# 1-voice_2_2.net
KiCad netlist of a schematic drawn in EAGLE
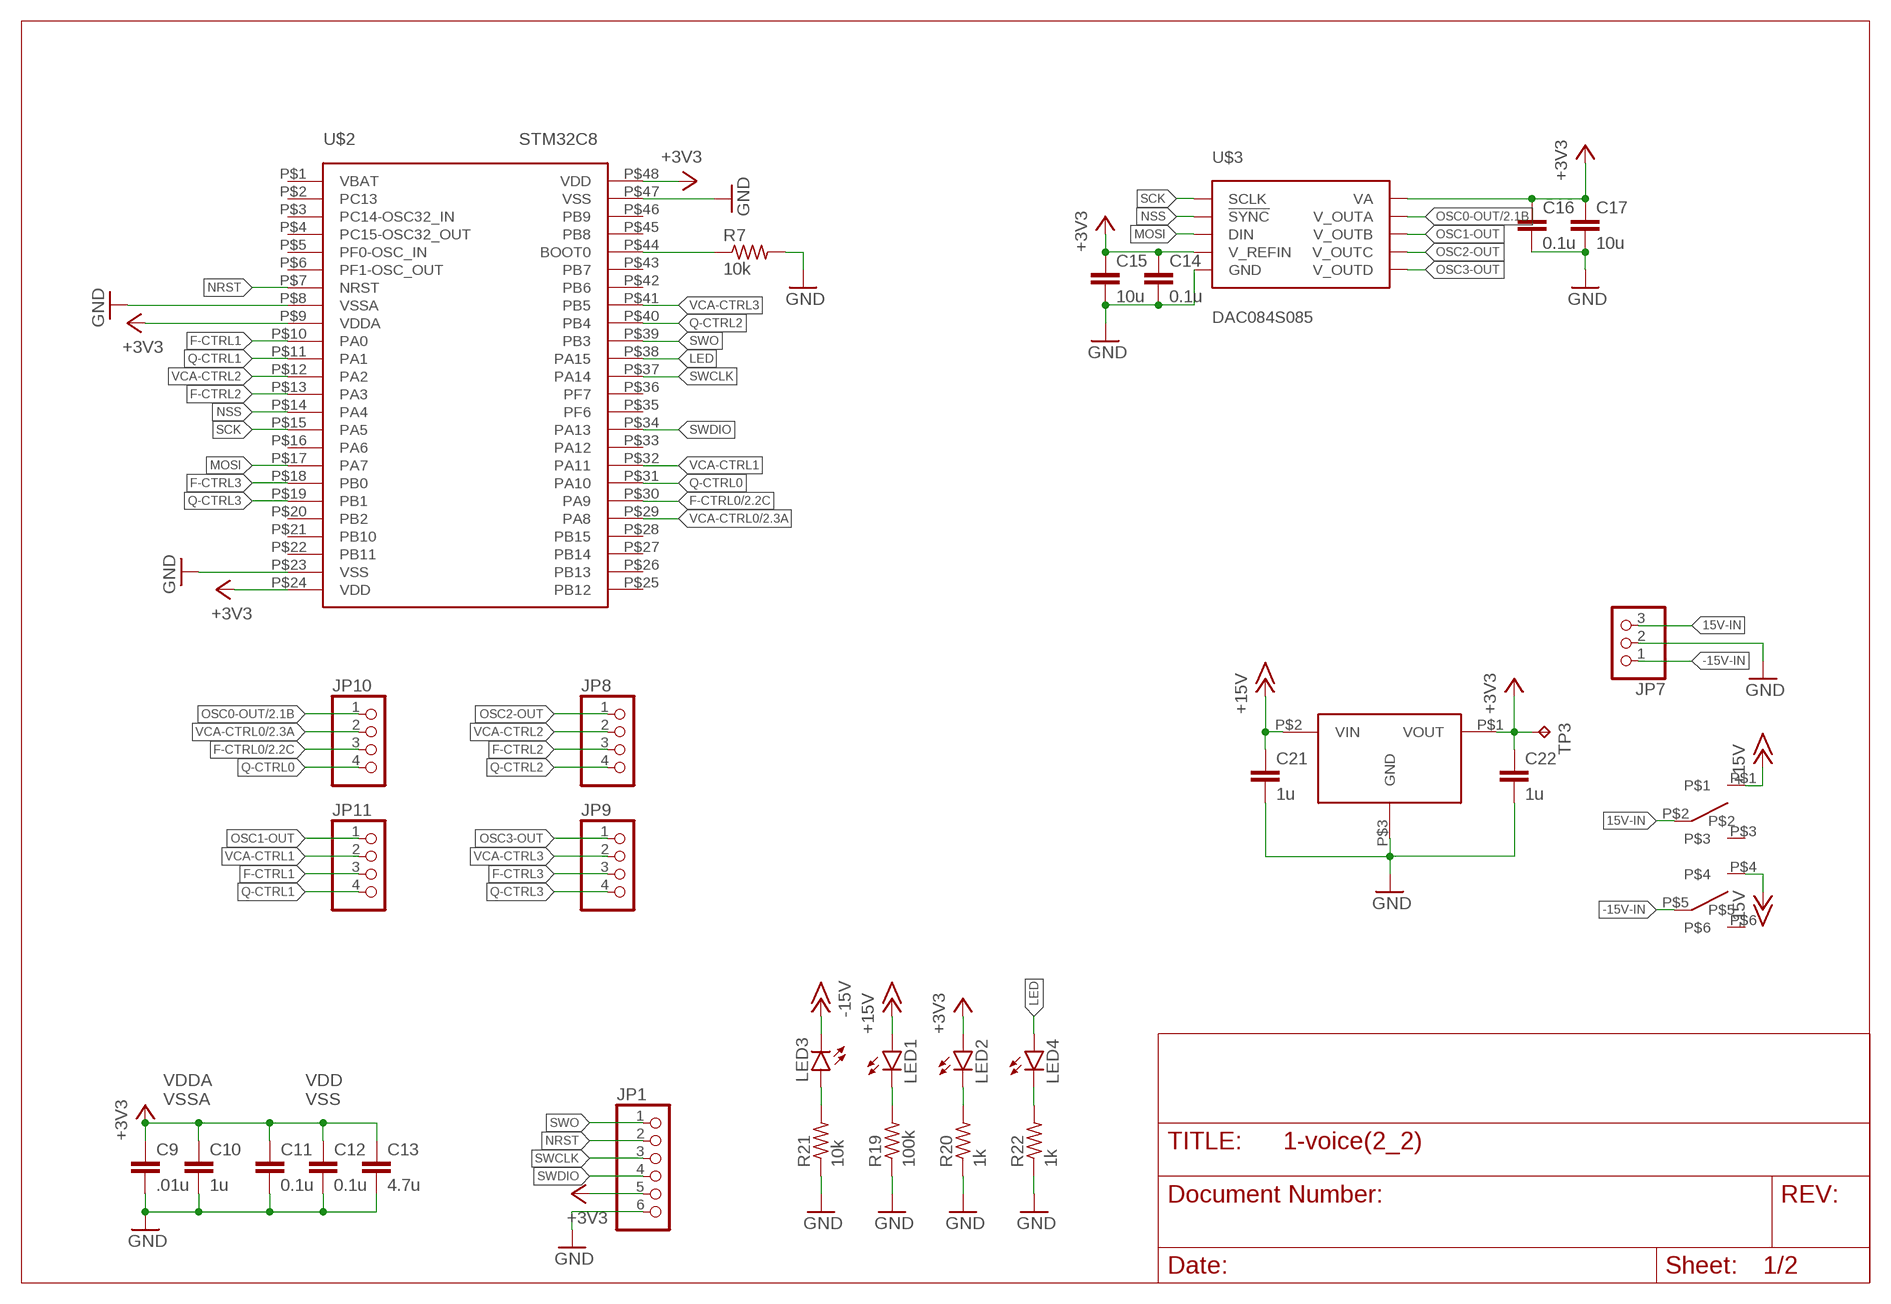
[diagram p0: schematic, sheet 1]
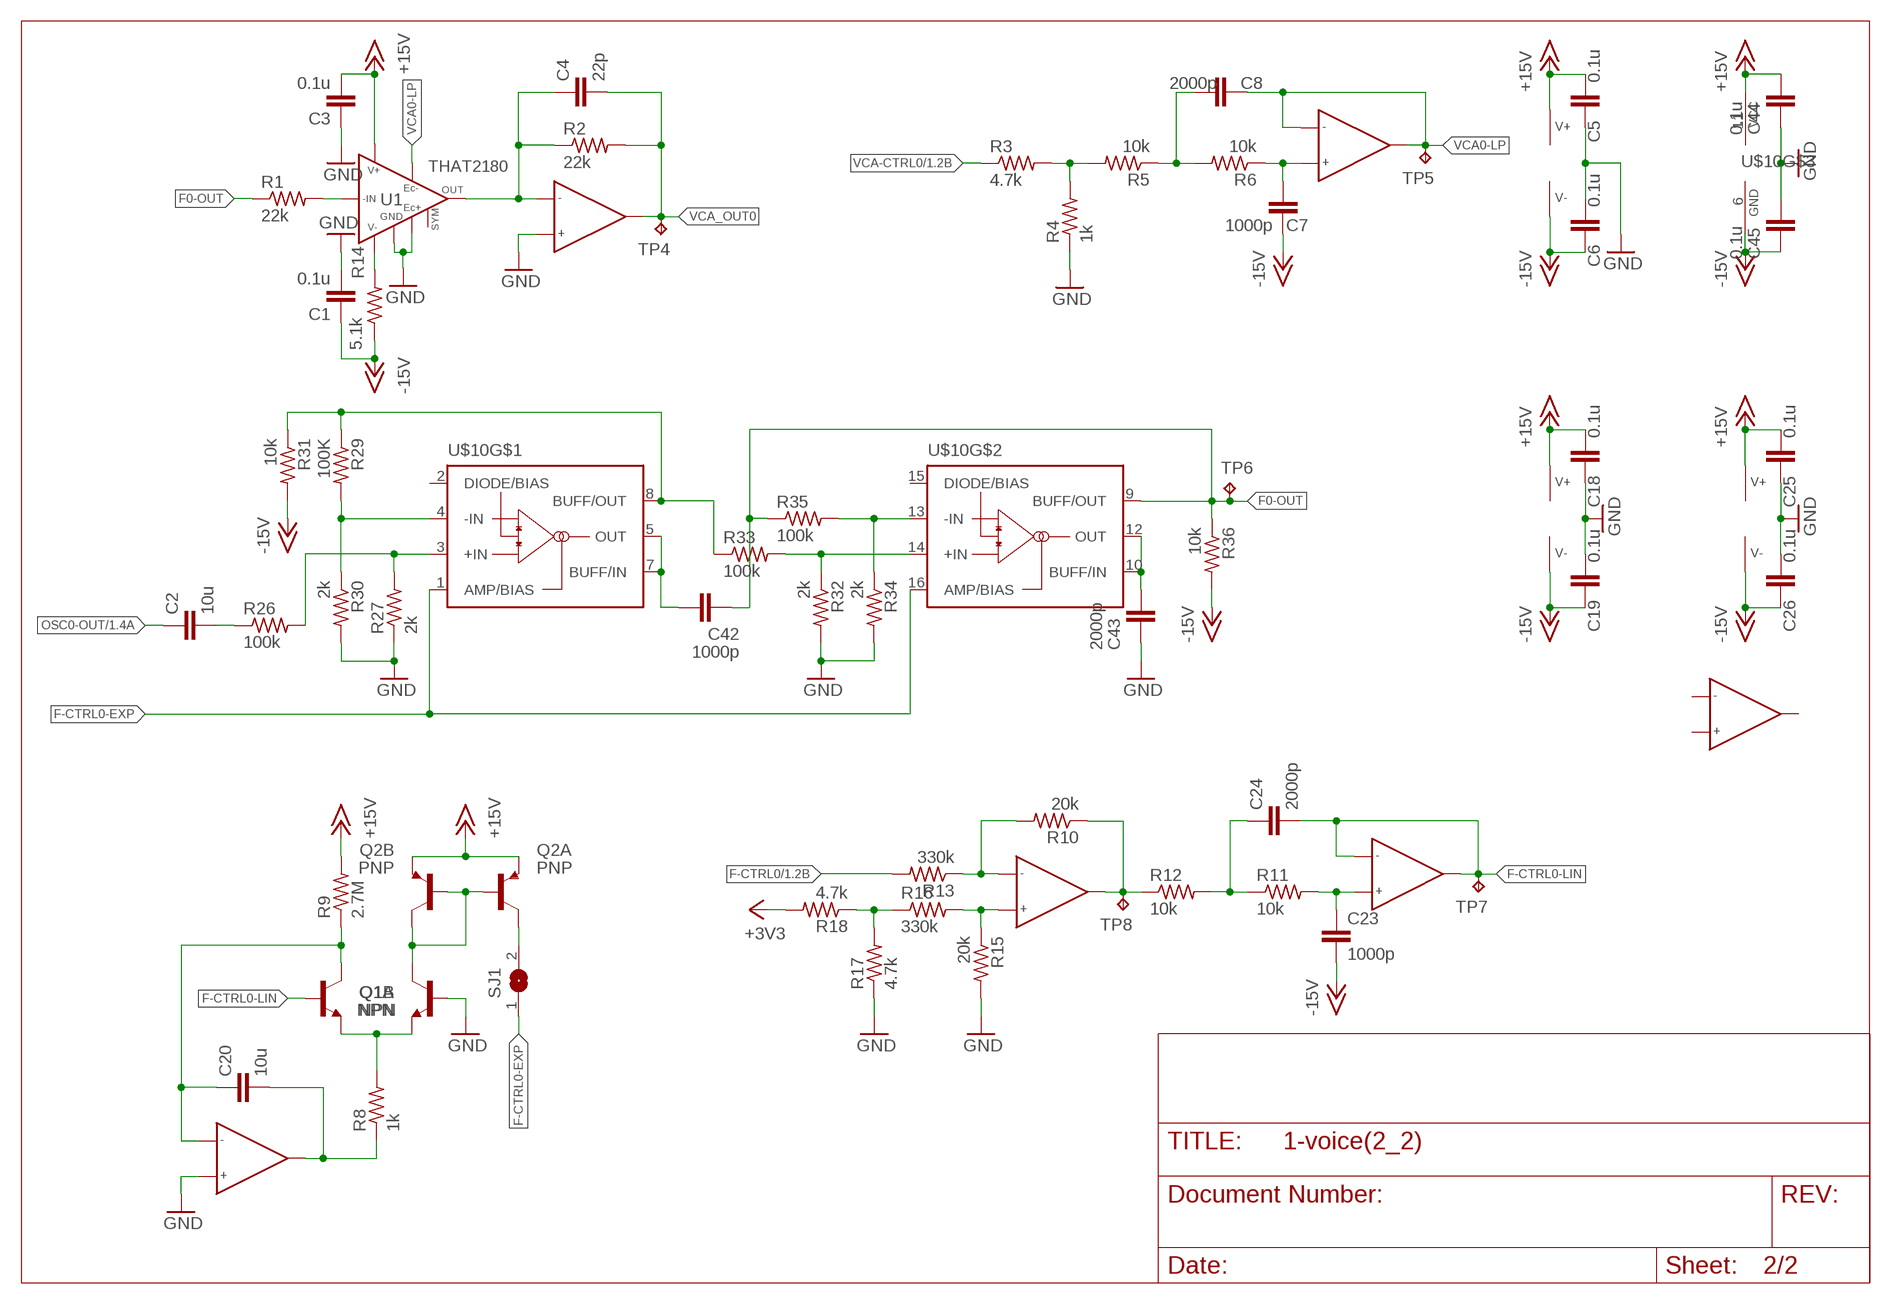
[diagram p1: schematic, sheet 2]

(export (version "E")
  (design (tool "Eeschema 10.0.6"))
  (components
    (comp (ref "C1")
      (value "0.1u")
      (footprint "eagle-import:C0603")
      (libsource (lib "eagle-import") (part "C-EUC0603"))
    )
    (comp (ref "C2")
      (value "10u")
      (footprint "eagle-import:C0603")
      (libsource (lib "eagle-import") (part "C-EUC0603"))
    )
    (comp (ref "C3")
      (value "0.1u")
      (footprint "eagle-import:C0603")
      (libsource (lib "eagle-import") (part "C-EUC0603"))
    )
    (comp (ref "C4")
      (value "22p")
      (footprint "eagle-import:C0603")
      (libsource (lib "eagle-import") (part "C-EUC0603"))
    )
    (comp (ref "C5")
      (value "0.1u")
      (footprint "eagle-import:C0603")
      (libsource (lib "eagle-import") (part "C-EUC0603"))
    )
    (comp (ref "C6")
      (value "0.1u")
      (footprint "eagle-import:C0603")
      (libsource (lib "eagle-import") (part "C-EUC0603"))
    )
    (comp (ref "C7")
      (value "1000p")
      (footprint "eagle-import:C0603")
      (libsource (lib "eagle-import") (part "C-EUC0603"))
    )
    (comp (ref "C8")
      (value "2000p")
      (footprint "eagle-import:C0603")
      (libsource (lib "eagle-import") (part "C-EUC0603"))
    )
    (comp (ref "C18")
      (value "0.1u")
      (footprint "eagle-import:C0603")
      (libsource (lib "eagle-import") (part "C-EUC0603"))
    )
    (comp (ref "C19")
      (value "0.1u")
      (footprint "eagle-import:C0603")
      (libsource (lib "eagle-import") (part "C-EUC0603"))
    )
    (comp (ref "C20")
      (value "10u")
      (footprint "eagle-import:C0603")
      (libsource (lib "eagle-import") (part "C-EUC0603"))
    )
    (comp (ref "C23")
      (value "1000p")
      (footprint "eagle-import:C0603")
      (libsource (lib "eagle-import") (part "C-EUC0603"))
    )
    (comp (ref "C24")
      (value "2000p")
      (footprint "eagle-import:C0603")
      (libsource (lib "eagle-import") (part "C-EUC0603"))
    )
    (comp (ref "C25")
      (value "0.1u")
      (footprint "eagle-import:C0603")
      (libsource (lib "eagle-import") (part "C-EUC0603"))
    )
    (comp (ref "C26")
      (value "0.1u")
      (footprint "eagle-import:C0603")
      (libsource (lib "eagle-import") (part "C-EUC0603"))
    )
    (comp (ref "C42")
      (value "1000p")
      (footprint "eagle-import:C0603")
      (libsource (lib "eagle-import") (part "C-EUC0603"))
    )
    (comp (ref "C43")
      (value "2000p")
      (footprint "eagle-import:C0603")
      (libsource (lib "eagle-import") (part "C-EUC0603"))
    )
    (comp (ref "C44")
      (value "0.1u")
      (footprint "eagle-import:C0603")
      (libsource (lib "eagle-import") (part "C-EUC0603"))
    )
    (comp (ref "C45")
      (value "0.1u")
      (footprint "eagle-import:C0603")
      (libsource (lib "eagle-import") (part "C-EUC0603"))
    )
    (comp (ref "Q1")
      (value "NPN")
      (footprint "eagle-import:SOT-363-JBLMASK")
      (libsource (lib "eagle-import") (part "TRANS-BJT_NPN-DUAL-BC847BS-JBLMASK"))
    )
    (comp (ref "Q2")
      (value "PNP")
      (footprint "eagle-import:SOT-363-JBLMASK")
      (libsource (lib "eagle-import") (part "TRANS-BJT_PNP-DUAL-BC857-JBLMASK"))
    )
    (comp (ref "R1")
      (value "22k")
      (footprint "eagle-import:R0603")
      (libsource (lib "eagle-import") (part "R-US_R0603"))
    )
    (comp (ref "R2")
      (value "22k")
      (footprint "eagle-import:R0603")
      (libsource (lib "eagle-import") (part "R-US_R0603"))
    )
    (comp (ref "R3")
      (value "4.7k")
      (footprint "eagle-import:R0603")
      (libsource (lib "eagle-import") (part "R-US_R0603"))
    )
    (comp (ref "R4")
      (value "1k")
      (footprint "eagle-import:R0603")
      (libsource (lib "eagle-import") (part "R-US_R0603"))
    )
    (comp (ref "R5")
      (value "10k")
      (footprint "eagle-import:R0603")
      (libsource (lib "eagle-import") (part "R-US_R0603"))
    )
    (comp (ref "R6")
      (value "10k")
      (footprint "eagle-import:R0603")
      (libsource (lib "eagle-import") (part "R-US_R0603"))
    )
    (comp (ref "R8")
      (value "1k")
      (footprint "eagle-import:R0603")
      (libsource (lib "eagle-import") (part "R-US_R0603"))
    )
    (comp (ref "R9")
      (value "2.7M")
      (footprint "eagle-import:R0603")
      (libsource (lib "eagle-import") (part "R-US_R0603"))
    )
    (comp (ref "R10")
      (value "20k")
      (footprint "eagle-import:R0603")
      (libsource (lib "eagle-import") (part "R-US_R0603"))
    )
    (comp (ref "R11")
      (value "10k")
      (footprint "eagle-import:R0603")
      (libsource (lib "eagle-import") (part "R-US_R0603"))
    )
    (comp (ref "R12")
      (value "10k")
      (footprint "eagle-import:R0603")
      (libsource (lib "eagle-import") (part "R-US_R0603"))
    )
    (comp (ref "R13")
      (value "330k")
      (footprint "eagle-import:R0603")
      (libsource (lib "eagle-import") (part "R-US_R0603"))
    )
    (comp (ref "R14")
      (value "5.1k")
      (footprint "eagle-import:R0603")
      (libsource (lib "eagle-import") (part "R-US_R0603"))
    )
    (comp (ref "R15")
      (value "20k")
      (footprint "eagle-import:R0603")
      (libsource (lib "eagle-import") (part "R-US_R0603"))
    )
    (comp (ref "R16")
      (value "330k")
      (footprint "eagle-import:R0603")
      (libsource (lib "eagle-import") (part "R-US_R0603"))
    )
    (comp (ref "R17")
      (value "4.7k")
      (footprint "eagle-import:R0603")
      (libsource (lib "eagle-import") (part "R-US_R0603"))
    )
    (comp (ref "R18")
      (value "4.7k")
      (footprint "eagle-import:R0603")
      (libsource (lib "eagle-import") (part "R-US_R0603"))
    )
    (comp (ref "R26")
      (value "100k")
      (footprint "eagle-import:R0603")
      (libsource (lib "eagle-import") (part "R-US_R0603"))
    )
    (comp (ref "R27")
      (value "2k")
      (footprint "eagle-import:R0603")
      (libsource (lib "eagle-import") (part "R-US_R0603"))
    )
    (comp (ref "R29")
      (value "100K")
      (footprint "eagle-import:R0603")
      (libsource (lib "eagle-import") (part "R-US_R0603"))
    )
    (comp (ref "R30")
      (value "2k")
      (footprint "eagle-import:R0603")
      (libsource (lib "eagle-import") (part "R-US_R0603"))
    )
    (comp (ref "R31")
      (value "10k")
      (footprint "eagle-import:R0603")
      (libsource (lib "eagle-import") (part "R-US_R0603"))
    )
    (comp (ref "R32")
      (value "2k")
      (footprint "eagle-import:R0603")
      (libsource (lib "eagle-import") (part "R-US_R0603"))
    )
    (comp (ref "R33")
      (value "100k")
      (footprint "eagle-import:R0603")
      (libsource (lib "eagle-import") (part "R-US_R0603"))
    )
    (comp (ref "R34")
      (value "2k")
      (footprint "eagle-import:R0603")
      (libsource (lib "eagle-import") (part "R-US_R0603"))
    )
    (comp (ref "R35")
      (value "100k")
      (footprint "eagle-import:R0603")
      (libsource (lib "eagle-import") (part "R-US_R0603"))
    )
    (comp (ref "R36")
      (value "10k")
      (footprint "eagle-import:R0603")
      (libsource (lib "eagle-import") (part "R-US_R0603"))
    )
    (comp (ref "SJ1") (value "SJ") (footprint "eagle-import:SJ") (libsource (lib "eagle-import") (part "SJ")))
    (comp (ref "TP4")
      (value "TPPAD1-13")
      (footprint "eagle-import:P1-13")
      (libsource (lib "eagle-import") (part "TPPAD1-13"))
    )
    (comp (ref "TP5")
      (value "TPPAD1-13")
      (footprint "eagle-import:P1-13")
      (libsource (lib "eagle-import") (part "TPPAD1-13"))
    )
    (comp (ref "TP6")
      (value "TPPAD1-13")
      (footprint "eagle-import:P1-13")
      (libsource (lib "eagle-import") (part "TPPAD1-13"))
    )
    (comp (ref "TP7")
      (value "TPPAD1-13")
      (footprint "eagle-import:P1-13")
      (libsource (lib "eagle-import") (part "TPPAD1-13"))
    )
    (comp (ref "TP8")
      (value "TPPAD1-13")
      (footprint "eagle-import:P1-13")
      (libsource (lib "eagle-import") (part "TPPAD1-13"))
    )
    (comp (ref "U$1")
      (value "TL072")
      (footprint "eagle-import:SOIC8")
      (libsource (lib "eagle-import") (part "TL072"))
    )
    (comp (ref "U$5")
      (value "TL072")
      (footprint "eagle-import:SOIC8")
      (libsource (lib "eagle-import") (part "TL072"))
    )
    (comp (ref "U$10")
      (value "XX-13700DMP16")
      (footprint "eagle-import:DMP16")
      (libsource (lib "eagle-import") (part "XX-13700DMP16"))
    )
    (comp (ref "U$11")
      (value "TL072")
      (footprint "eagle-import:SOIC8")
      (libsource (lib "eagle-import") (part "TL072"))
    )
    (comp (ref "U1")
      (value "THAT2180")
      (footprint "eagle-import:SIP8")
      (libsource (lib "eagle-import") (part "THAT2180"))
    )
    (comp (ref "C9")
      (value ".01u")
      (footprint "eagle-import:C0603")
      (libsource (lib "eagle-import") (part "C-EUC0603"))
    )
    (comp (ref "C10")
      (value "1u")
      (footprint "eagle-import:C0603")
      (libsource (lib "eagle-import") (part "C-EUC0603"))
    )
    (comp (ref "C11")
      (value "0.1u")
      (footprint "eagle-import:C0603")
      (libsource (lib "eagle-import") (part "C-EUC0603"))
    )
    (comp (ref "C12")
      (value "0.1u")
      (footprint "eagle-import:C0603")
      (libsource (lib "eagle-import") (part "C-EUC0603"))
    )
    (comp (ref "C13")
      (value "4.7u")
      (footprint "eagle-import:C0603")
      (libsource (lib "eagle-import") (part "C-EUC0603"))
    )
    (comp (ref "C14")
      (value "0.1u")
      (footprint "eagle-import:C0603")
      (libsource (lib "eagle-import") (part "C-EUC0603"))
    )
    (comp (ref "C15")
      (value "10u")
      (footprint "eagle-import:C0603")
      (libsource (lib "eagle-import") (part "C-EUC0603"))
    )
    (comp (ref "C16")
      (value "0.1u")
      (footprint "eagle-import:C0603")
      (libsource (lib "eagle-import") (part "C-EUC0603"))
    )
    (comp (ref "C17")
      (value "10u")
      (footprint "eagle-import:C0603")
      (libsource (lib "eagle-import") (part "C-EUC0603"))
    )
    (comp (ref "C21")
      (value "1u")
      (footprint "eagle-import:C0603")
      (libsource (lib "eagle-import") (part "C-EUC0603"))
    )
    (comp (ref "C22")
      (value "1u")
      (footprint "eagle-import:C0603")
      (libsource (lib "eagle-import") (part "C-EUC0603"))
    )
    (comp (ref "JP1")
      (value "PINHD-1X6")
      (footprint "eagle-import:1X06")
      (libsource (lib "eagle-import") (part "PINHD-1X6"))
    )
    (comp (ref "JP7")
      (value "PINHD-1X3")
      (footprint "eagle-import:1X03")
      (libsource (lib "eagle-import") (part "PINHD-1X3"))
    )
    (comp (ref "JP8")
      (value "PINHD-1X4")
      (footprint "eagle-import:1X04")
      (libsource (lib "eagle-import") (part "PINHD-1X4"))
    )
    (comp (ref "JP9")
      (value "PINHD-1X4")
      (footprint "eagle-import:1X04")
      (libsource (lib "eagle-import") (part "PINHD-1X4"))
    )
    (comp (ref "JP10")
      (value "PINHD-1X4")
      (footprint "eagle-import:1X04")
      (libsource (lib "eagle-import") (part "PINHD-1X4"))
    )
    (comp (ref "JP11")
      (value "PINHD-1X4")
      (footprint "eagle-import:1X04")
      (libsource (lib "eagle-import") (part "PINHD-1X4"))
    )
    (comp (ref "LED1")
      (value "LEDSMT1206")
      (footprint "eagle-import:1206")
      (libsource (lib "eagle-import") (part "LEDSMT1206"))
    )
    (comp (ref "LED2")
      (value "LEDSMT1206")
      (footprint "eagle-import:1206")
      (libsource (lib "eagle-import") (part "LEDSMT1206"))
    )
    (comp (ref "LED3")
      (value "LEDSMT1206")
      (footprint "eagle-import:1206")
      (libsource (lib "eagle-import") (part "LEDSMT1206"))
    )
    (comp (ref "LED4")
      (value "LEDSMT1206")
      (footprint "eagle-import:1206")
      (libsource (lib "eagle-import") (part "LEDSMT1206"))
    )
    (comp (ref "R7")
      (value "10k")
      (footprint "eagle-import:R0603")
      (libsource (lib "eagle-import") (part "R-US_R0603"))
    )
    (comp (ref "R19")
      (value "100k")
      (footprint "eagle-import:R0603")
      (libsource (lib "eagle-import") (part "R-US_R0603"))
    )
    (comp (ref "R20")
      (value "1k")
      (footprint "eagle-import:R0603")
      (libsource (lib "eagle-import") (part "R-US_R0603"))
    )
    (comp (ref "R21")
      (value "10k")
      (footprint "eagle-import:R0603")
      (libsource (lib "eagle-import") (part "R-US_R0603"))
    )
    (comp (ref "R22")
      (value "1k")
      (footprint "eagle-import:R0603")
      (libsource (lib "eagle-import") (part "R-US_R0603"))
    )
    (comp (ref "TP3")
      (value "TPPAD1-13")
      (footprint "eagle-import:P1-13")
      (libsource (lib "eagle-import") (part "TPPAD1-13"))
    )
    (comp (ref "U$2")
      (value "STM32C8")
      (footprint "eagle-import:LQFP48")
      (libsource (lib "eagle-import") (part "STM32C8"))
    )
    (comp (ref "U$3")
      (value "DAC084S085")
      (footprint "eagle-import:VSSOP10")
      (libsource (lib "eagle-import") (part "DAC084S085"))
    )
    (comp (ref "U$4")
      (value "TLV760")
      (footprint "eagle-import:SOT23-3")
      (libsource (lib "eagle-import") (part "TLV760"))
    )
    (comp (ref "U$6")
      (value "SWITCH-DPDT")
      (footprint "eagle-import:DPDT")
      (libsource (lib "eagle-import") (part "SWITCH-DPDT"))
    )
  )
  (nets
    (net (code "1") (name "+3V3") (class "Default")
      (node (ref "C10") (pin "1") (pinfunction "1_1") (pintype "passive"))
      (node (ref "C11") (pin "1") (pinfunction "1_1") (pintype "passive"))
      (node (ref "C12") (pin "1") (pinfunction "1_1") (pintype "passive"))
      (node (ref "C13") (pin "1") (pinfunction "1_1") (pintype "passive"))
      (node (ref "C14") (pin "1") (pinfunction "1_1") (pintype "passive"))
      (node (ref "C15") (pin "1") (pinfunction "1_1") (pintype "passive"))
      (node (ref "C16") (pin "1") (pinfunction "1_1") (pintype "passive"))
      (node (ref "C17") (pin "1") (pinfunction "1_1") (pintype "passive"))
      (node (ref "C22") (pin "1") (pinfunction "1_1") (pintype "passive"))
      (node (ref "C9") (pin "1") (pinfunction "1_1") (pintype "passive"))
      (node (ref "JP1") (pin "5") (pinfunction "5_5") (pintype "passive"))
      (node (ref "LED2") (pin "A") (pinfunction "A_A") (pintype "passive"))
      (node (ref "R18") (pin "2") (pinfunction "2_2") (pintype "passive"))
      (node (ref "TP3") (pin "TP") (pinfunction "TP_TP") (pintype "input"))
      (node (ref "U$2") (pin "P$24") (pinfunction "VDD_P$24") (pintype "bidirectional"))
      (node (ref "U$2") (pin "P$48") (pinfunction "VDD_P$48") (pintype "bidirectional"))
      (node (ref "U$2") (pin "P$9") (pinfunction "VDDA_P$9") (pintype "bidirectional"))
      (node (ref "U$3") (pin "P$1") (pinfunction "VA_P$1") (pintype "bidirectional"))
      (node (ref "U$3") (pin "P$7") (pinfunction "V_REFIN_P$7") (pintype "bidirectional"))
      (node (ref "U$4") (pin "P$1") (pinfunction "VOUT_P$1") (pintype "bidirectional"))
    )
    (net (code "2") (name "+15V") (class "Default")
      (node (ref "C18") (pin "2") (pinfunction "2_2") (pintype "passive"))
      (node (ref "C21") (pin "1") (pinfunction "1_1") (pintype "passive"))
      (node (ref "C25") (pin "2") (pinfunction "2_2") (pintype "passive"))
      (node (ref "C3") (pin "2") (pinfunction "2_2") (pintype "passive"))
      (node (ref "C44") (pin "1") (pinfunction "1_1") (pintype "passive"))
      (node (ref "C5") (pin "2") (pinfunction "2_2") (pintype "passive"))
      (node (ref "LED1") (pin "A") (pinfunction "A_A") (pintype "passive"))
      (node (ref "Q2") (pin "1") (pinfunction "E_1") (pintype "passive"))
      (node (ref "Q2") (pin "4") (pinfunction "E_4") (pintype "passive"))
      (node (ref "R9") (pin "2") (pinfunction "2_2") (pintype "passive"))
      (node (ref "U$1") (pin "P$8") (pinfunction "V+_P$8") (pintype "bidirectional"))
      (node (ref "U$10") (pin "11") (pinfunction "VCC_11") (pintype "power_in"))
      (node (ref "U$11") (pin "P$8") (pinfunction "V+_P$8") (pintype "bidirectional"))
      (node (ref "U$4") (pin "P$2") (pinfunction "VIN_P$2") (pintype "bidirectional"))
      (node (ref "U$5") (pin "P$8") (pinfunction "V+_P$8") (pintype "bidirectional"))
      (node (ref "U$6") (pin "P$1") (pinfunction "P$1_P$1") (pintype "bidirectional"))
      (node (ref "U1") (pin "$P7") (pinfunction "V+_$P7") (pintype "bidirectional"))
    )
    (net (code "3") (name "-15V") (class "Default")
      (node (ref "C1") (pin "1") (pinfunction "1_1") (pintype "passive"))
      (node (ref "C19") (pin "1") (pinfunction "1_1") (pintype "passive"))
      (node (ref "C23") (pin "2") (pinfunction "2_2") (pintype "passive"))
      (node (ref "C26") (pin "1") (pinfunction "1_1") (pintype "passive"))
      (node (ref "C45") (pin "2") (pinfunction "2_2") (pintype "passive"))
      (node (ref "C6") (pin "1") (pinfunction "1_1") (pintype "passive"))
      (node (ref "C7") (pin "1") (pinfunction "1_1") (pintype "passive"))
      (node (ref "LED3") (pin "C") (pinfunction "C_C") (pintype "passive"))
      (node (ref "R14") (pin "1") (pinfunction "1_1") (pintype "passive"))
      (node (ref "R31") (pin "2") (pinfunction "2_2") (pintype "passive"))
      (node (ref "R36") (pin "2") (pinfunction "2_2") (pintype "passive"))
      (node (ref "U$1") (pin "P$4") (pinfunction "V-_P$4") (pintype "bidirectional"))
      (node (ref "U$10") (pin "6") (pinfunction "GND_6") (pintype "power_in"))
      (node (ref "U$11") (pin "P$4") (pinfunction "V-_P$4") (pintype "bidirectional"))
      (node (ref "U$5") (pin "P$4") (pinfunction "V-_P$4") (pintype "bidirectional"))
      (node (ref "U$6") (pin "P$4") (pinfunction "P$4_P$4") (pintype "bidirectional"))
    )
    (net (code "4") (name "-15V-IN") (class "Default")
      (node (ref "JP7") (pin "1") (pinfunction "1_1") (pintype "passive"))
      (node (ref "U$6") (pin "P$5") (pinfunction "P$5_P$5") (pintype "bidirectional"))
    )
    (net (code "5") (name "15V-IN") (class "Default")
      (node (ref "JP7") (pin "3") (pinfunction "3_3") (pintype "passive"))
      (node (ref "U$6") (pin "P$2") (pinfunction "P$2_P$2") (pintype "bidirectional"))
    )
    (net (code "6") (name "F-CTRL0") (class "Default")
      (node (ref "JP10") (pin "3") (pinfunction "3_3") (pintype "passive"))
      (node (ref "R13") (pin "2") (pinfunction "2_2") (pintype "passive"))
      (node (ref "U$2") (pin "P$30") (pinfunction "PA9_P$30") (pintype "bidirectional"))
    )
    (net (code "7") (name "F-CTRL0-EXP") (class "Default")
      (node (ref "SJ1") (pin "1") (pinfunction "1_1") (pintype "passive"))
      (node (ref "U$10") (pin "1") (pinfunction "AMP/BIAS_1") (pintype "passive"))
      (node (ref "U$10") (pin "16") (pinfunction "AMP/BIAS_16") (pintype "passive"))
    )
    (net (code "8") (name "F-CTRL0-LIN") (class "Default")
      (node (ref "C24") (pin "2") (pinfunction "2_2") (pintype "passive"))
      (node (ref "Q1") (pin "2") (pinfunction "B_2") (pintype "passive"))
      (node (ref "TP7") (pin "TP") (pinfunction "TP_TP") (pintype "input"))
      (node (ref "U$11") (pin "P$6") (pinfunction "IN-_P$6") (pintype "bidirectional"))
      (node (ref "U$11") (pin "P$7") (pinfunction "OUT_P$7") (pintype "bidirectional"))
    )
    (net (code "9") (name "F-CTRL1") (class "Default")
      (node (ref "JP11") (pin "3") (pinfunction "3_3") (pintype "passive"))
      (node (ref "U$2") (pin "P$10") (pinfunction "PA0_P$10") (pintype "bidirectional"))
    )
    (net (code "10") (name "F-CTRL2") (class "Default")
      (node (ref "JP8") (pin "3") (pinfunction "3_3") (pintype "passive"))
      (node (ref "U$2") (pin "P$13") (pinfunction "PA3_P$13") (pintype "bidirectional"))
    )
    (net (code "11") (name "F-CTRL3") (class "Default")
      (node (ref "JP9") (pin "3") (pinfunction "3_3") (pintype "passive"))
      (node (ref "U$2") (pin "P$18") (pinfunction "PB0_P$18") (pintype "bidirectional"))
    )
    (net (code "12") (name "F0-OUT") (class "Default")
      (node (ref "C42") (pin "2") (pinfunction "2_2") (pintype "passive"))
      (node (ref "R1") (pin "1") (pinfunction "1_1") (pintype "passive"))
      (node (ref "R35") (pin "1") (pinfunction "1_1") (pintype "passive"))
      (node (ref "R36") (pin "1") (pinfunction "1_1") (pintype "passive"))
      (node (ref "TP6") (pin "TP") (pinfunction "TP_TP") (pintype "input"))
      (node (ref "U$10") (pin "9") (pinfunction "BUFF/OUT_9") (pintype "output"))
    )
    (net (code "13") (name "GND") (class "Default")
      (node (ref "C1") (pin "2") (pinfunction "2_2") (pintype "passive"))
      (node (ref "C10") (pin "2") (pinfunction "2_2") (pintype "passive"))
      (node (ref "C11") (pin "2") (pinfunction "2_2") (pintype "passive"))
      (node (ref "C12") (pin "2") (pinfunction "2_2") (pintype "passive"))
      (node (ref "C13") (pin "2") (pinfunction "2_2") (pintype "passive"))
      (node (ref "C14") (pin "2") (pinfunction "2_2") (pintype "passive"))
      (node (ref "C15") (pin "2") (pinfunction "2_2") (pintype "passive"))
      (node (ref "C16") (pin "2") (pinfunction "2_2") (pintype "passive"))
      (node (ref "C17") (pin "2") (pinfunction "2_2") (pintype "passive"))
      (node (ref "C18") (pin "1") (pinfunction "1_1") (pintype "passive"))
      (node (ref "C19") (pin "2") (pinfunction "2_2") (pintype "passive"))
      (node (ref "C21") (pin "2") (pinfunction "2_2") (pintype "passive"))
      (node (ref "C22") (pin "2") (pinfunction "2_2") (pintype "passive"))
      (node (ref "C25") (pin "1") (pinfunction "1_1") (pintype "passive"))
      (node (ref "C26") (pin "2") (pinfunction "2_2") (pintype "passive"))
      (node (ref "C3") (pin "1") (pinfunction "1_1") (pintype "passive"))
      (node (ref "C43") (pin "2") (pinfunction "2_2") (pintype "passive"))
      (node (ref "C44") (pin "2") (pinfunction "2_2") (pintype "passive"))
      (node (ref "C45") (pin "1") (pinfunction "1_1") (pintype "passive"))
      (node (ref "C5") (pin "1") (pinfunction "1_1") (pintype "passive"))
      (node (ref "C6") (pin "2") (pinfunction "2_2") (pintype "passive"))
      (node (ref "C9") (pin "2") (pinfunction "2_2") (pintype "passive"))
      (node (ref "JP1") (pin "6") (pinfunction "6_6") (pintype "passive"))
      (node (ref "JP7") (pin "2") (pinfunction "2_2") (pintype "passive"))
      (node (ref "Q1") (pin "5") (pinfunction "B_5") (pintype "passive"))
      (node (ref "R15") (pin "2") (pinfunction "2_2") (pintype "passive"))
      (node (ref "R17") (pin "1") (pinfunction "1_1") (pintype "passive"))
      (node (ref "R19") (pin "1") (pinfunction "1_1") (pintype "passive"))
      (node (ref "R20") (pin "1") (pinfunction "1_1") (pintype "passive"))
      (node (ref "R21") (pin "1") (pinfunction "1_1") (pintype "passive"))
      (node (ref "R22") (pin "1") (pinfunction "1_1") (pintype "passive"))
      (node (ref "R27") (pin "1") (pinfunction "1_1") (pintype "passive"))
      (node (ref "R30") (pin "2") (pinfunction "2_2") (pintype "passive"))
      (node (ref "R32") (pin "2") (pinfunction "2_2") (pintype "passive"))
      (node (ref "R34") (pin "2") (pinfunction "2_2") (pintype "passive"))
      (node (ref "R4") (pin "1") (pinfunction "1_1") (pintype "passive"))
      (node (ref "R7") (pin "2") (pinfunction "2_2") (pintype "passive"))
      (node (ref "U$1") (pin "P$3") (pinfunction "IN+_P$3") (pintype "bidirectional"))
      (node (ref "U$11") (pin "P$3") (pinfunction "IN+_P$3") (pintype "bidirectional"))
      (node (ref "U$2") (pin "P$23") (pinfunction "VSS_P$23") (pintype "bidirectional"))
      (node (ref "U$2") (pin "P$47") (pinfunction "VSS_P$47") (pintype "bidirectional"))
      (node (ref "U$2") (pin "P$8") (pinfunction "VSSA_P$8") (pintype "bidirectional"))
      (node (ref "U$3") (pin "P$6") (pinfunction "GND_P$6") (pintype "bidirectional"))
      (node (ref "U$4") (pin "P$3") (pinfunction "GND_P$3") (pintype "bidirectional"))
      (node (ref "U1") (pin "$P2") (pinfunction "EC+_$P2") (pintype "bidirectional"))
      (node (ref "U1") (pin "$P6") (pinfunction "GND_$P6") (pintype "bidirectional"))
    )
    (net (code "14") (name "LED") (class "Default")
      (node (ref "LED4") (pin "A") (pinfunction "A_A") (pintype "passive"))
      (node (ref "U$2") (pin "P$38") (pinfunction "PA15_P$38") (pintype "bidirectional"))
    )
    (net (code "15") (name "MOSI") (class "Default")
      (node (ref "U$2") (pin "P$17") (pinfunction "PA7_P$17") (pintype "bidirectional"))
      (node (ref "U$3") (pin "P$8") (pinfunction "DIN_P$8") (pintype "bidirectional"))
    )
    (net (code "16") (name "NRST") (class "Default")
      (node (ref "JP1") (pin "2") (pinfunction "2_2") (pintype "passive"))
      (node (ref "U$2") (pin "P$7") (pinfunction "NRST_P$7") (pintype "bidirectional"))
    )
    (net (code "17") (name "NSS") (class "Default")
      (node (ref "U$2") (pin "P$14") (pinfunction "PA4_P$14") (pintype "bidirectional"))
      (node (ref "U$3") (pin "P$9") (pinfunction "~{SYNC}_P$9") (pintype "bidirectional"))
    )
    (net (code "18") (name "Net-(C2-Pad2)") (class "Default")
      (node (ref "C2") (pin "2") (pinfunction "2_2") (pintype "passive"))
      (node (ref "R26") (pin "1") (pinfunction "1_1") (pintype "passive"))
    )
    (net (code "19") (name "Net-(C8-Pad2)") (class "Default")
      (node (ref "C8") (pin "2") (pinfunction "2_2") (pintype "passive"))
      (node (ref "R5") (pin "1") (pinfunction "1_1") (pintype "passive"))
      (node (ref "R6") (pin "2") (pinfunction "2_2") (pintype "passive"))
    )
    (net (code "20") (name "Net-(C24-Pad1)") (class "Default")
      (node (ref "C24") (pin "1") (pinfunction "1_1") (pintype "passive"))
      (node (ref "R11") (pin "1") (pinfunction "1_1") (pintype "passive"))
      (node (ref "R12") (pin "2") (pinfunction "2_2") (pintype "passive"))
    )
    (net (code "21") (name "Net-(LED1-PadC)") (class "Default")
      (node (ref "LED1") (pin "C") (pinfunction "C_C") (pintype "passive"))
      (node (ref "R19") (pin "2") (pinfunction "2_2") (pintype "passive"))
    )
    (net (code "22") (name "Net-(LED2-PadC)") (class "Default")
      (node (ref "LED2") (pin "C") (pinfunction "C_C") (pintype "passive"))
      (node (ref "R20") (pin "2") (pinfunction "2_2") (pintype "passive"))
    )
    (net (code "23") (name "Net-(LED3-PadA)") (class "Default")
      (node (ref "LED3") (pin "A") (pinfunction "A_A") (pintype "passive"))
      (node (ref "R21") (pin "2") (pinfunction "2_2") (pintype "passive"))
    )
    (net (code "24") (name "Net-(LED4-PadC)") (class "Default")
      (node (ref "LED4") (pin "C") (pinfunction "C_C") (pintype "passive"))
      (node (ref "R22") (pin "2") (pinfunction "2_2") (pintype "passive"))
    )
    (net (code "25") (name "Net-(Q1A-C)") (class "Default")
      (node (ref "C20") (pin "1") (pinfunction "1_1") (pintype "passive"))
      (node (ref "Q1") (pin "6") (pinfunction "C_6") (pintype "passive"))
      (node (ref "R9") (pin "1") (pinfunction "1_1") (pintype "passive"))
      (node (ref "U$11") (pin "P$2") (pinfunction "IN-_P$2") (pintype "bidirectional"))
    )
    (net (code "26") (name "Net-(Q1A-E)") (class "Default")
      (node (ref "Q1") (pin "1") (pinfunction "E_1") (pintype "passive"))
      (node (ref "Q1") (pin "4") (pinfunction "E_4") (pintype "passive"))
      (node (ref "R8") (pin "2") (pinfunction "2_2") (pintype "passive"))
    )
    (net (code "27") (name "Net-(Q1B-C)") (class "Default")
      (node (ref "Q1") (pin "3") (pinfunction "C_3") (pintype "passive"))
      (node (ref "Q2") (pin "2") (pinfunction "B_2") (pintype "passive"))
      (node (ref "Q2") (pin "3") (pinfunction "C_3") (pintype "passive"))
      (node (ref "Q2") (pin "5") (pinfunction "B_5") (pintype "passive"))
    )
    (net (code "28") (name "Net-(Q2A-C)") (class "Default")
      (node (ref "Q2") (pin "6") (pinfunction "C_6") (pintype "passive"))
      (node (ref "SJ1") (pin "2") (pinfunction "2_2") (pintype "passive"))
    )
    (net (code "29") (name "Net-(R3-Pad2)") (class "Default")
      (node (ref "R3") (pin "2") (pinfunction "2_2") (pintype "passive"))
      (node (ref "R4") (pin "2") (pinfunction "2_2") (pintype "passive"))
      (node (ref "R5") (pin "2") (pinfunction "2_2") (pintype "passive"))
    )
    (net (code "30") (name "Net-(R16-Pad1)") (class "Default")
      (node (ref "R16") (pin "1") (pinfunction "1_1") (pintype "passive"))
      (node (ref "R17") (pin "2") (pinfunction "2_2") (pintype "passive"))
      (node (ref "R18") (pin "1") (pinfunction "1_1") (pintype "passive"))
    )
    (net (code "31") (name "Net-(U$1A-IN-)") (class "Default")
      (node (ref "C4") (pin "1") (pinfunction "1_1") (pintype "passive"))
      (node (ref "R2") (pin "1") (pinfunction "1_1") (pintype "passive"))
      (node (ref "U$1") (pin "P$2") (pinfunction "IN-_P$2") (pintype "bidirectional"))
      (node (ref "U1") (pin "$P8") (pinfunction "OUT_$P8") (pintype "bidirectional"))
    )
    (net (code "32") (name "Net-(U$1B-IN+)") (class "Default")
      (node (ref "C7") (pin "2") (pinfunction "2_2") (pintype "passive"))
      (node (ref "R6") (pin "1") (pinfunction "1_1") (pintype "passive"))
      (node (ref "U$1") (pin "P$5") (pinfunction "IN+_P$5") (pintype "bidirectional"))
    )
    (net (code "33") (name "Net-(U$2-BOOT0)") (class "Default")
      (node (ref "R7") (pin "1") (pinfunction "1_1") (pintype "passive"))
      (node (ref "U$2") (pin "P$44") (pinfunction "BOOT0_P$44") (pintype "bidirectional"))
    )
    (net (code "34") (name "Net-(U$5B-IN+)") (class "Default")
      (node (ref "R15") (pin "1") (pinfunction "1_1") (pintype "passive"))
      (node (ref "R16") (pin "2") (pinfunction "2_2") (pintype "passive"))
      (node (ref "U$5") (pin "P$5") (pinfunction "IN+_P$5") (pintype "bidirectional"))
    )
    (net (code "35") (name "Net-(U$5B-IN-)") (class "Default")
      (node (ref "R10") (pin "2") (pinfunction "2_2") (pintype "passive"))
      (node (ref "R13") (pin "1") (pinfunction "1_1") (pintype "passive"))
      (node (ref "U$5") (pin "P$6") (pinfunction "IN-_P$6") (pintype "bidirectional"))
    )
    (net (code "36") (name "Net-(U$5B-OUT)") (class "Default")
      (node (ref "R10") (pin "1") (pinfunction "1_1") (pintype "passive"))
      (node (ref "R12") (pin "1") (pinfunction "1_1") (pintype "passive"))
      (node (ref "TP8") (pin "TP") (pinfunction "TP_TP") (pintype "input"))
      (node (ref "U$5") (pin "P$7") (pinfunction "OUT_P$7") (pintype "bidirectional"))
    )
    (net (code "37") (name "Net-(U$10A-+IN)") (class "Default")
      (node (ref "R26") (pin "2") (pinfunction "2_2") (pintype "passive"))
      (node (ref "R27") (pin "2") (pinfunction "2_2") (pintype "passive"))
      (node (ref "U$10") (pin "3") (pinfunction "+IN_3") (pintype "input"))
    )
    (net (code "38") (name "Net-(U$10A--IN)") (class "Default")
      (node (ref "R29") (pin "2") (pinfunction "2_2") (pintype "passive"))
      (node (ref "R30") (pin "1") (pinfunction "1_1") (pintype "passive"))
      (node (ref "U$10") (pin "4") (pinfunction "-IN_4") (pintype "input"))
    )
    (net (code "39") (name "Net-(U$10A-BUFF{slash}IN)") (class "Default")
      (node (ref "C42") (pin "1") (pinfunction "1_1") (pintype "passive"))
      (node (ref "U$10") (pin "5") (pinfunction "OUT_5") (pintype "output"))
      (node (ref "U$10") (pin "7") (pinfunction "BUFF/IN_7") (pintype "input"))
    )
    (net (code "40") (name "Net-(U$10A-BUFF{slash}OUT)") (class "Default")
      (node (ref "R29") (pin "1") (pinfunction "1_1") (pintype "passive"))
      (node (ref "R31") (pin "1") (pinfunction "1_1") (pintype "passive"))
      (node (ref "R33") (pin "1") (pinfunction "1_1") (pintype "passive"))
      (node (ref "U$10") (pin "8") (pinfunction "BUFF/OUT_8") (pintype "output"))
    )
    (net (code "41") (name "Net-(U$10B-+IN)") (class "Default")
      (node (ref "R32") (pin "1") (pinfunction "1_1") (pintype "passive"))
      (node (ref "R33") (pin "2") (pinfunction "2_2") (pintype "passive"))
      (node (ref "U$10") (pin "14") (pinfunction "+IN_14") (pintype "input"))
    )
    (net (code "42") (name "Net-(U$10B--IN)") (class "Default")
      (node (ref "R34") (pin "1") (pinfunction "1_1") (pintype "passive"))
      (node (ref "R35") (pin "2") (pinfunction "2_2") (pintype "passive"))
      (node (ref "U$10") (pin "13") (pinfunction "-IN_13") (pintype "input"))
    )
    (net (code "43") (name "Net-(U$10B-BUFF{slash}IN)") (class "Default")
      (node (ref "C43") (pin "1") (pinfunction "1_1") (pintype "passive"))
      (node (ref "U$10") (pin "10") (pinfunction "BUFF/IN_10") (pintype "input"))
      (node (ref "U$10") (pin "12") (pinfunction "OUT_12") (pintype "output"))
    )
    (net (code "44") (name "Net-(U$11A-OUT)") (class "Default")
      (node (ref "C20") (pin "2") (pinfunction "2_2") (pintype "passive"))
      (node (ref "R8") (pin "1") (pinfunction "1_1") (pintype "passive"))
      (node (ref "U$11") (pin "P$1") (pinfunction "OUT_P$1") (pintype "bidirectional"))
    )
    (net (code "45") (name "Net-(U$11B-IN+)") (class "Default")
      (node (ref "C23") (pin "1") (pinfunction "1_1") (pintype "passive"))
      (node (ref "R11") (pin "2") (pinfunction "2_2") (pintype "passive"))
      (node (ref "U$11") (pin "P$5") (pinfunction "IN+_P$5") (pintype "bidirectional"))
    )
    (net (code "46") (name "Net-(U1--IN)") (class "Default")
      (node (ref "R1") (pin "2") (pinfunction "2_2") (pintype "passive"))
      (node (ref "U1") (pin "$P1") (pinfunction "-IN_$P1") (pintype "bidirectional"))
    )
    (net (code "47") (name "Net-(U1-V-)") (class "Default")
      (node (ref "R14") (pin "2") (pinfunction "2_2") (pintype "passive"))
      (node (ref "U1") (pin "$P5") (pinfunction "V-_$P5") (pintype "bidirectional"))
    )
    (net (code "48") (name "OSC0-OUT") (class "Default")
      (node (ref "C2") (pin "1") (pinfunction "1_1") (pintype "passive"))
      (node (ref "JP10") (pin "1") (pinfunction "1_1") (pintype "passive"))
      (node (ref "U$3") (pin "P$2") (pinfunction "V_OUTA_P$2") (pintype "bidirectional"))
    )
    (net (code "49") (name "OSC1-OUT") (class "Default")
      (node (ref "JP11") (pin "1") (pinfunction "1_1") (pintype "passive"))
      (node (ref "U$3") (pin "P$3") (pinfunction "V_OUTB_P$3") (pintype "bidirectional"))
    )
    (net (code "50") (name "OSC2-OUT") (class "Default")
      (node (ref "JP8") (pin "1") (pinfunction "1_1") (pintype "passive"))
      (node (ref "U$3") (pin "P$4") (pinfunction "V_OUTC_P$4") (pintype "bidirectional"))
    )
    (net (code "51") (name "OSC3-OUT") (class "Default")
      (node (ref "JP9") (pin "1") (pinfunction "1_1") (pintype "passive"))
      (node (ref "U$3") (pin "P$5") (pinfunction "V_OUTD_P$5") (pintype "bidirectional"))
    )
    (net (code "52") (name "Q-CTRL0") (class "Default")
      (node (ref "JP10") (pin "4") (pinfunction "4_4") (pintype "passive"))
      (node (ref "U$2") (pin "P$31") (pinfunction "PA10_P$31") (pintype "bidirectional"))
    )
    (net (code "53") (name "Q-CTRL1") (class "Default")
      (node (ref "JP11") (pin "4") (pinfunction "4_4") (pintype "passive"))
      (node (ref "U$2") (pin "P$11") (pinfunction "PA1_P$11") (pintype "bidirectional"))
    )
    (net (code "54") (name "Q-CTRL2") (class "Default")
      (node (ref "JP8") (pin "4") (pinfunction "4_4") (pintype "passive"))
      (node (ref "U$2") (pin "P$40") (pinfunction "PB4_P$40") (pintype "bidirectional"))
    )
    (net (code "55") (name "Q-CTRL3") (class "Default")
      (node (ref "JP9") (pin "4") (pinfunction "4_4") (pintype "passive"))
      (node (ref "U$2") (pin "P$19") (pinfunction "PB1_P$19") (pintype "bidirectional"))
    )
    (net (code "56") (name "SCK") (class "Default")
      (node (ref "U$2") (pin "P$15") (pinfunction "PA5_P$15") (pintype "bidirectional"))
      (node (ref "U$3") (pin "P$10") (pinfunction "SCLK_P$10") (pintype "bidirectional"))
    )
    (net (code "57") (name "SWCLK") (class "Default")
      (node (ref "JP1") (pin "3") (pinfunction "3_3") (pintype "passive"))
      (node (ref "U$2") (pin "P$37") (pinfunction "PA14_P$37") (pintype "bidirectional"))
    )
    (net (code "58") (name "SWDIO") (class "Default")
      (node (ref "JP1") (pin "4") (pinfunction "4_4") (pintype "passive"))
      (node (ref "U$2") (pin "P$34") (pinfunction "PA13_P$34") (pintype "bidirectional"))
    )
    (net (code "59") (name "SWO") (class "Default")
      (node (ref "JP1") (pin "1") (pinfunction "1_1") (pintype "passive"))
      (node (ref "U$2") (pin "P$39") (pinfunction "PB3_P$39") (pintype "bidirectional"))
    )
    (net (code "60") (name "VCA-CTRL0") (class "Default")
      (node (ref "JP10") (pin "2") (pinfunction "2_2") (pintype "passive"))
      (node (ref "R3") (pin "1") (pinfunction "1_1") (pintype "passive"))
      (node (ref "U$2") (pin "P$29") (pinfunction "PA8_P$29") (pintype "bidirectional"))
    )
    (net (code "61") (name "VCA-CTRL1") (class "Default")
      (node (ref "JP11") (pin "2") (pinfunction "2_2") (pintype "passive"))
      (node (ref "U$2") (pin "P$32") (pinfunction "PA11_P$32") (pintype "bidirectional"))
    )
    (net (code "62") (name "VCA-CTRL2") (class "Default")
      (node (ref "JP8") (pin "2") (pinfunction "2_2") (pintype "passive"))
      (node (ref "U$2") (pin "P$12") (pinfunction "PA2_P$12") (pintype "bidirectional"))
    )
    (net (code "63") (name "VCA-CTRL3") (class "Default")
      (node (ref "JP9") (pin "2") (pinfunction "2_2") (pintype "passive"))
      (node (ref "U$2") (pin "P$41") (pinfunction "PB5_P$41") (pintype "bidirectional"))
    )
    (net (code "64") (name "VCA0-LP") (class "Default")
      (node (ref "C8") (pin "1") (pinfunction "1_1") (pintype "passive"))
      (node (ref "TP5") (pin "TP") (pinfunction "TP_TP") (pintype "input"))
      (node (ref "U$1") (pin "P$6") (pinfunction "IN-_P$6") (pintype "bidirectional"))
      (node (ref "U$1") (pin "P$7") (pinfunction "OUT_P$7") (pintype "bidirectional"))
      (node (ref "U1") (pin "$P3") (pinfunction "EC-_$P3") (pintype "bidirectional"))
    )
    (net (code "65") (name "VCA_OUT0") (class "Default")
      (node (ref "C4") (pin "2") (pinfunction "2_2") (pintype "passive"))
      (node (ref "R2") (pin "2") (pinfunction "2_2") (pintype "passive"))
      (node (ref "TP4") (pin "TP") (pinfunction "TP_TP") (pintype "input"))
      (node (ref "U$1") (pin "P$1") (pinfunction "OUT_P$1") (pintype "bidirectional"))
    )
    (net (code "66") (name "unconnected-(U$2-PA6-PadP$16)") (class "Default")
      (node (ref "U$2") (pin "P$16") (pinfunction "PA6_P$16") (pintype "bidirectional"))
    )
    (net (code "67") (name "unconnected-(U$2-PA12-PadP$33)") (class "Default")
      (node (ref "U$2") (pin "P$33") (pinfunction "PA12_P$33") (pintype "bidirectional"))
    )
    (net (code "68") (name "unconnected-(U$2-PB2-PadP$20)") (class "Default")
      (node (ref "U$2") (pin "P$20") (pinfunction "PB2_P$20") (pintype "bidirectional"))
    )
    (net (code "69") (name "unconnected-(U$2-PB6-PadP$42)") (class "Default")
      (node (ref "U$2") (pin "P$42") (pinfunction "PB6_P$42") (pintype "bidirectional"))
    )
    (net (code "70") (name "unconnected-(U$2-PB7-PadP$43)") (class "Default")
      (node (ref "U$2") (pin "P$43") (pinfunction "PB7_P$43") (pintype "bidirectional"))
    )
    (net (code "71") (name "unconnected-(U$2-PB8-PadP$45)") (class "Default")
      (node (ref "U$2") (pin "P$45") (pinfunction "PB8_P$45") (pintype "bidirectional"))
    )
    (net (code "72") (name "unconnected-(U$2-PB9-PadP$46)") (class "Default")
      (node (ref "U$2") (pin "P$46") (pinfunction "PB9_P$46") (pintype "bidirectional"))
    )
    (net (code "73") (name "unconnected-(U$2-PB10-PadP$21)") (class "Default")
      (node (ref "U$2") (pin "P$21") (pinfunction "PB10_P$21") (pintype "bidirectional"))
    )
    (net (code "74") (name "unconnected-(U$2-PB11-PadP$22)") (class "Default")
      (node (ref "U$2") (pin "P$22") (pinfunction "PB11_P$22") (pintype "bidirectional"))
    )
    (net (code "75") (name "unconnected-(U$2-PB12-PadP$25)") (class "Default")
      (node (ref "U$2") (pin "P$25") (pinfunction "PB12_P$25") (pintype "bidirectional"))
    )
    (net (code "76") (name "unconnected-(U$2-PB13-PadP$26)") (class "Default")
      (node (ref "U$2") (pin "P$26") (pinfunction "PB13_P$26") (pintype "bidirectional"))
    )
    (net (code "77") (name "unconnected-(U$2-PB14-PadP$27)") (class "Default")
      (node (ref "U$2") (pin "P$27") (pinfunction "PB14_P$27") (pintype "bidirectional"))
    )
    (net (code "78") (name "unconnected-(U$2-PB15-PadP$28)") (class "Default")
      (node (ref "U$2") (pin "P$28") (pinfunction "PB15_P$28") (pintype "bidirectional"))
    )
    (net (code "79") (name "unconnected-(U$2-PC13-PadP$2)") (class "Default")
      (node (ref "U$2") (pin "P$2") (pinfunction "PC13_P$2") (pintype "bidirectional"))
    )
    (net (code "80") (name "unconnected-(U$2-PC14-OSC32_IN-PadP$3)") (class "Default")
      (node (ref "U$2") (pin "P$3") (pinfunction "PC14-OSC32_IN_P$3") (pintype "bidirectional"))
    )
    (net (code "81") (name "unconnected-(U$2-PC15-OSC32_OUT-PadP$4)") (class "Default")
      (node (ref "U$2") (pin "P$4") (pinfunction "PC15-OSC32_OUT_P$4") (pintype "bidirectional"))
    )
    (net (code "82") (name "unconnected-(U$2-PF0-OSC_IN-PadP$5)") (class "Default")
      (node (ref "U$2") (pin "P$5") (pinfunction "PF0-OSC_IN_P$5") (pintype "bidirectional"))
    )
    (net (code "83") (name "unconnected-(U$2-PF1-OSC_OUT-PadP$6)") (class "Default")
      (node (ref "U$2") (pin "P$6") (pinfunction "PF1-OSC_OUT_P$6") (pintype "bidirectional"))
    )
    (net (code "84") (name "unconnected-(U$2-PF6-PadP$35)") (class "Default")
      (node (ref "U$2") (pin "P$35") (pinfunction "PF6_P$35") (pintype "bidirectional"))
    )
    (net (code "85") (name "unconnected-(U$2-PF7-PadP$36)") (class "Default")
      (node (ref "U$2") (pin "P$36") (pinfunction "PF7_P$36") (pintype "bidirectional"))
    )
    (net (code "86") (name "unconnected-(U$2-VBAT-PadP$1)") (class "Default")
      (node (ref "U$2") (pin "P$1") (pinfunction "VBAT_P$1") (pintype "bidirectional"))
    )
    (net (code "87") (name "unconnected-(U$5A-IN+-PadP$3)") (class "Default")
      (node (ref "U$5") (pin "P$3") (pinfunction "IN+_P$3") (pintype "bidirectional"))
    )
    (net (code "88") (name "unconnected-(U$5A-IN--PadP$2)") (class "Default")
      (node (ref "U$5") (pin "P$2") (pinfunction "IN-_P$2") (pintype "bidirectional"))
    )
    (net (code "89") (name "unconnected-(U$5A-OUT-PadP$1)") (class "Default")
      (node (ref "U$5") (pin "P$1") (pinfunction "OUT_P$1") (pintype "bidirectional"))
    )
    (net (code "90") (name "unconnected-(U$6-PadP$3)") (class "Default")
      (node (ref "U$6") (pin "P$3") (pinfunction "P$3_P$3") (pintype "bidirectional"))
    )
    (net (code "91") (name "unconnected-(U$6-PadP$6)") (class "Default")
      (node (ref "U$6") (pin "P$6") (pinfunction "P$6_P$6") (pintype "bidirectional"))
    )
    (net (code "92") (name "unconnected-(U$10A-DIODE{slash}BIAS-Pad2)") (class "Default")
      (node (ref "U$10") (pin "2") (pinfunction "DIODE/BIAS_2") (pintype "passive"))
    )
    (net (code "93") (name "unconnected-(U$10B-DIODE{slash}BIAS-Pad15)") (class "Default")
      (node (ref "U$10") (pin "15") (pinfunction "DIODE/BIAS_15") (pintype "passive"))
    )
    (net (code "94") (name "unconnected-(U1-SYM-Pad$P4)") (class "Default")
      (node (ref "U1") (pin "$P4") (pinfunction "SYM_$P4") (pintype "bidirectional"))
    )
  )
)
